# eib-64-large.net
KiCad netlist of a schematic drawn in EAGLE
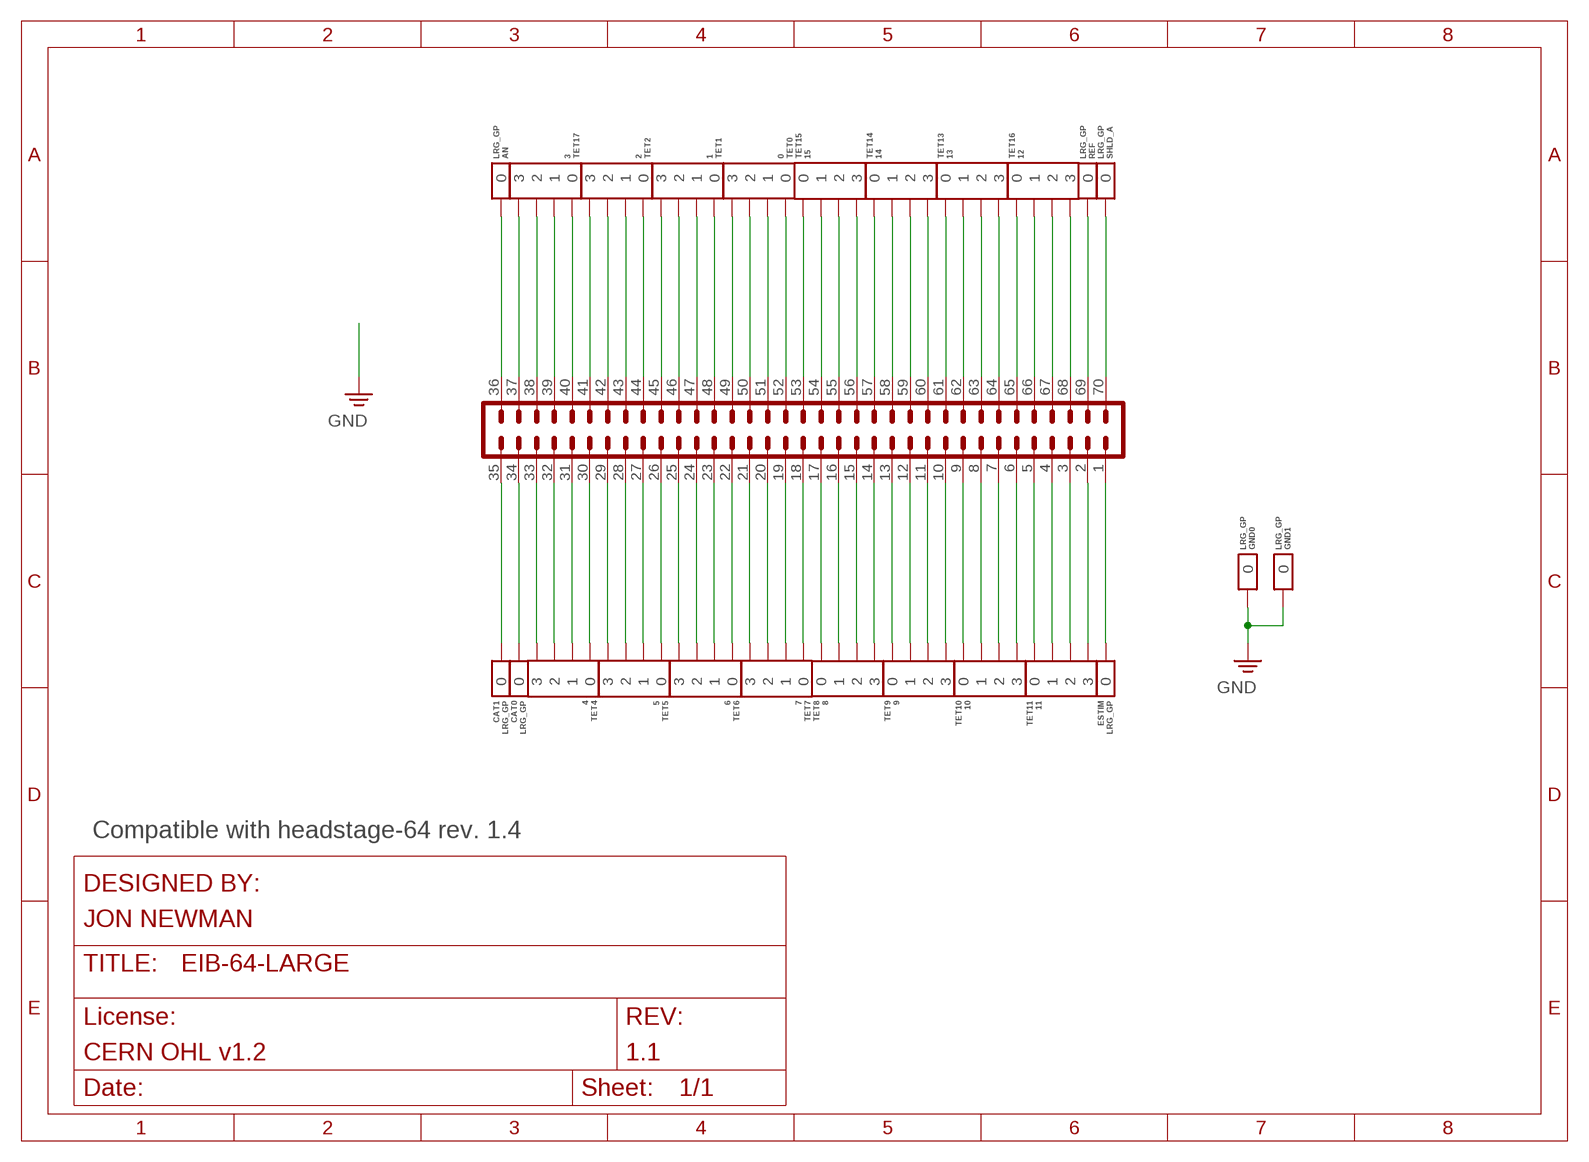
[diagram p0: schematic, sheet 1]

(export (version "E")
  (design (tool "Eeschema 10.0.6"))
  (components
    (comp (ref "AN")
      (value "LRG_GP")
      (footprint "eagle-import:GOLDPIN_0.5ID_0.7OD")
      (libsource (lib "eagle-import") (part "GOLDPIN_0.5ID_0.7OD"))
    )
    (comp (ref "CAT0")
      (value "LRG_GP")
      (footprint "eagle-import:GOLDPIN_0.5ID_0.7OD")
      (libsource (lib "eagle-import") (part "GOLDPIN_0.5ID_0.7OD"))
    )
    (comp (ref "CAT1")
      (value "LRG_GP")
      (footprint "eagle-import:GOLDPIN_0.5ID_0.7OD")
      (libsource (lib "eagle-import") (part "GOLDPIN_0.5ID_0.7OD"))
    )
    (comp (ref "ESTIM")
      (value "LRG_GP")
      (footprint "eagle-import:GOLDPIN_0.5ID_0.7OD")
      (libsource (lib "eagle-import") (part "GOLDPIN_0.5ID_0.7OD"))
    )
    (comp (ref "GND0")
      (value "LRG_GP")
      (footprint "eagle-import:GOLDPIN_0.5ID_0.7OD")
      (libsource (lib "eagle-import") (part "GOLDPIN_0.5ID_0.7OD"))
    )
    (comp (ref "GND1")
      (value "LRG_GP")
      (footprint "eagle-import:GOLDPIN_0.5ID_0.7OD")
      (libsource (lib "eagle-import") (part "GOLDPIN_0.5ID_0.7OD"))
    )
    (comp (ref "J1")
      (value "DF40-REC")
      (footprint "eagle-import:DDF40-70REC-LRG")
      (libsource (lib "eagle-import") (part "PINHD-2X35_DF40REF-LRG"))
    )
    (comp (ref "REF")
      (value "LRG_GP")
      (footprint "eagle-import:GOLDPIN_0.5ID_0.7OD")
      (libsource (lib "eagle-import") (part "GOLDPIN_0.5ID_0.7OD"))
    )
    (comp (ref "SHLD_A")
      (value "LRG_GP")
      (footprint "eagle-import:GOLDPIN_0.5ID_0.7OD")
      (libsource (lib "eagle-import") (part "GOLDPIN_0.5ID_0.7OD"))
    )
    (comp (ref "TET0")
      (value "0")
      (footprint "eagle-import:TETRODE_128_0.5ID_0.7OD")
      (libsource (lib "eagle-import") (part "TETRODE_128_0.5ID_0.7OD"))
    )
    (comp (ref "TET1")
      (value "1")
      (footprint "eagle-import:TETRODE_128_0.5ID_0.7OD")
      (libsource (lib "eagle-import") (part "TETRODE_128_0.5ID_0.7OD"))
    )
    (comp (ref "TET2")
      (value "2")
      (footprint "eagle-import:TETRODE_128_0.5ID_0.7OD")
      (libsource (lib "eagle-import") (part "TETRODE_128_0.5ID_0.7OD"))
    )
    (comp (ref "TET4")
      (value "4")
      (footprint "eagle-import:TETRODE_128_0.5ID_0.7OD")
      (libsource (lib "eagle-import") (part "TETRODE_128_0.5ID_0.7OD"))
    )
    (comp (ref "TET5")
      (value "5")
      (footprint "eagle-import:TETRODE_128_0.5ID_0.7OD")
      (libsource (lib "eagle-import") (part "TETRODE_128_0.5ID_0.7OD"))
    )
    (comp (ref "TET6")
      (value "6")
      (footprint "eagle-import:TETRODE_128_0.5ID_0.7OD")
      (libsource (lib "eagle-import") (part "TETRODE_128_0.5ID_0.7OD"))
    )
    (comp (ref "TET7")
      (value "7")
      (footprint "eagle-import:TETRODE_128_0.5ID_0.7OD")
      (libsource (lib "eagle-import") (part "TETRODE_128_0.5ID_0.7OD"))
    )
    (comp (ref "TET8")
      (value "8")
      (footprint "eagle-import:TETRODE_128_0.5ID_0.7OD")
      (libsource (lib "eagle-import") (part "TETRODE_128_0.5ID_0.7OD"))
    )
    (comp (ref "TET9")
      (value "9")
      (footprint "eagle-import:TETRODE_128_0.5ID_0.7OD")
      (libsource (lib "eagle-import") (part "TETRODE_128_0.5ID_0.7OD"))
    )
    (comp (ref "TET10")
      (value "10")
      (footprint "eagle-import:TETRODE_128_0.5ID_0.7OD")
      (libsource (lib "eagle-import") (part "TETRODE_128_0.5ID_0.7OD"))
    )
    (comp (ref "TET11")
      (value "11")
      (footprint "eagle-import:TETRODE_128_0.5ID_0.7OD")
      (libsource (lib "eagle-import") (part "TETRODE_128_0.5ID_0.7OD"))
    )
    (comp (ref "TET13")
      (value "13")
      (footprint "eagle-import:TETRODE_128_0.5ID_0.7OD")
      (libsource (lib "eagle-import") (part "TETRODE_128_0.5ID_0.7OD"))
    )
    (comp (ref "TET14")
      (value "14")
      (footprint "eagle-import:TETRODE_128_0.5ID_0.7OD")
      (libsource (lib "eagle-import") (part "TETRODE_128_0.5ID_0.7OD"))
    )
    (comp (ref "TET15")
      (value "15")
      (footprint "eagle-import:TETRODE_128_0.5ID_0.7OD")
      (libsource (lib "eagle-import") (part "TETRODE_128_0.5ID_0.7OD"))
    )
    (comp (ref "TET16")
      (value "12")
      (footprint "eagle-import:TETRODE_128_0.5ID_0.7OD")
      (libsource (lib "eagle-import") (part "TETRODE_128_0.5ID_0.7OD"))
    )
    (comp (ref "TET17")
      (value "3")
      (footprint "eagle-import:TETRODE_128_0.5ID_0.7OD")
      (libsource (lib "eagle-import") (part "TETRODE_128_0.5ID_0.7OD"))
    )
  )
  (nets
    (net (code "1") (name "GND") (class "Default")
      (node (ref "GND0") (pin "P$1") (pinfunction "0_P$1") (pintype "bidirectional"))
      (node (ref "GND1") (pin "P$1") (pinfunction "0_P$1") (pintype "bidirectional"))
    )
    (net (code "2") (name "Net-(AN-0)") (class "Default")
      (node (ref "AN") (pin "P$1") (pinfunction "0_P$1") (pintype "bidirectional"))
      (node (ref "J1") (pin "36") (pinfunction "36_36") (pintype "bidirectional"))
    )
    (net (code "3") (name "Net-(CAT0-0)") (class "Default")
      (node (ref "CAT0") (pin "P$1") (pinfunction "0_P$1") (pintype "bidirectional"))
      (node (ref "J1") (pin "34") (pinfunction "34_34") (pintype "bidirectional"))
    )
    (net (code "4") (name "Net-(CAT1-0)") (class "Default")
      (node (ref "CAT1") (pin "P$1") (pinfunction "0_P$1") (pintype "bidirectional"))
      (node (ref "J1") (pin "35") (pinfunction "35_35") (pintype "bidirectional"))
    )
    (net (code "5") (name "Net-(ESTIM-0)") (class "Default")
      (node (ref "ESTIM") (pin "P$1") (pinfunction "0_P$1") (pintype "bidirectional"))
      (node (ref "J1") (pin "1") (pinfunction "1_1") (pintype "bidirectional"))
    )
    (net (code "6") (name "Net-(J1-Pad2)") (class "Default")
      (node (ref "J1") (pin "2") (pinfunction "2_2") (pintype "bidirectional"))
      (node (ref "TET11") (pin "3") (pinfunction "3_3") (pintype "bidirectional"))
    )
    (net (code "7") (name "Net-(J1-Pad3)") (class "Default")
      (node (ref "J1") (pin "3") (pinfunction "3_3") (pintype "bidirectional"))
      (node (ref "TET11") (pin "2") (pinfunction "2_2") (pintype "bidirectional"))
    )
    (net (code "8") (name "Net-(J1-Pad4)") (class "Default")
      (node (ref "J1") (pin "4") (pinfunction "4_4") (pintype "bidirectional"))
      (node (ref "TET11") (pin "1") (pinfunction "1_1") (pintype "bidirectional"))
    )
    (net (code "9") (name "Net-(J1-Pad5)") (class "Default")
      (node (ref "J1") (pin "5") (pinfunction "5_5") (pintype "bidirectional"))
      (node (ref "TET11") (pin "0") (pinfunction "0_0") (pintype "bidirectional"))
    )
    (net (code "10") (name "Net-(J1-Pad6)") (class "Default")
      (node (ref "J1") (pin "6") (pinfunction "6_6") (pintype "bidirectional"))
      (node (ref "TET10") (pin "3") (pinfunction "3_3") (pintype "bidirectional"))
    )
    (net (code "11") (name "Net-(J1-Pad7)") (class "Default")
      (node (ref "J1") (pin "7") (pinfunction "7_7") (pintype "bidirectional"))
      (node (ref "TET10") (pin "2") (pinfunction "2_2") (pintype "bidirectional"))
    )
    (net (code "12") (name "Net-(J1-Pad8)") (class "Default")
      (node (ref "J1") (pin "8") (pinfunction "8_8") (pintype "bidirectional"))
      (node (ref "TET10") (pin "1") (pinfunction "1_1") (pintype "bidirectional"))
    )
    (net (code "13") (name "Net-(J1-Pad9)") (class "Default")
      (node (ref "J1") (pin "9") (pinfunction "9_9") (pintype "bidirectional"))
      (node (ref "TET10") (pin "0") (pinfunction "0_0") (pintype "bidirectional"))
    )
    (net (code "14") (name "Net-(J1-Pad10)") (class "Default")
      (node (ref "J1") (pin "10") (pinfunction "10_10") (pintype "bidirectional"))
      (node (ref "TET9") (pin "3") (pinfunction "3_3") (pintype "bidirectional"))
    )
    (net (code "15") (name "Net-(J1-Pad11)") (class "Default")
      (node (ref "J1") (pin "11") (pinfunction "11_11") (pintype "bidirectional"))
      (node (ref "TET9") (pin "2") (pinfunction "2_2") (pintype "bidirectional"))
    )
    (net (code "16") (name "Net-(J1-Pad12)") (class "Default")
      (node (ref "J1") (pin "12") (pinfunction "12_12") (pintype "bidirectional"))
      (node (ref "TET9") (pin "1") (pinfunction "1_1") (pintype "bidirectional"))
    )
    (net (code "17") (name "Net-(J1-Pad13)") (class "Default")
      (node (ref "J1") (pin "13") (pinfunction "13_13") (pintype "bidirectional"))
      (node (ref "TET9") (pin "0") (pinfunction "0_0") (pintype "bidirectional"))
    )
    (net (code "18") (name "Net-(J1-Pad14)") (class "Default")
      (node (ref "J1") (pin "14") (pinfunction "14_14") (pintype "bidirectional"))
      (node (ref "TET8") (pin "3") (pinfunction "3_3") (pintype "bidirectional"))
    )
    (net (code "19") (name "Net-(J1-Pad15)") (class "Default")
      (node (ref "J1") (pin "15") (pinfunction "15_15") (pintype "bidirectional"))
      (node (ref "TET8") (pin "2") (pinfunction "2_2") (pintype "bidirectional"))
    )
    (net (code "20") (name "Net-(J1-Pad16)") (class "Default")
      (node (ref "J1") (pin "16") (pinfunction "16_16") (pintype "bidirectional"))
      (node (ref "TET8") (pin "1") (pinfunction "1_1") (pintype "bidirectional"))
    )
    (net (code "21") (name "Net-(J1-Pad17)") (class "Default")
      (node (ref "J1") (pin "17") (pinfunction "17_17") (pintype "bidirectional"))
      (node (ref "TET8") (pin "0") (pinfunction "0_0") (pintype "bidirectional"))
    )
    (net (code "22") (name "Net-(J1-Pad18)") (class "Default")
      (node (ref "J1") (pin "18") (pinfunction "18_18") (pintype "bidirectional"))
      (node (ref "TET7") (pin "0") (pinfunction "0_0") (pintype "bidirectional"))
    )
    (net (code "23") (name "Net-(J1-Pad19)") (class "Default")
      (node (ref "J1") (pin "19") (pinfunction "19_19") (pintype "bidirectional"))
      (node (ref "TET7") (pin "1") (pinfunction "1_1") (pintype "bidirectional"))
    )
    (net (code "24") (name "Net-(J1-Pad20)") (class "Default")
      (node (ref "J1") (pin "20") (pinfunction "20_20") (pintype "bidirectional"))
      (node (ref "TET7") (pin "2") (pinfunction "2_2") (pintype "bidirectional"))
    )
    (net (code "25") (name "Net-(J1-Pad21)") (class "Default")
      (node (ref "J1") (pin "21") (pinfunction "21_21") (pintype "bidirectional"))
      (node (ref "TET7") (pin "3") (pinfunction "3_3") (pintype "bidirectional"))
    )
    (net (code "26") (name "Net-(J1-Pad22)") (class "Default")
      (node (ref "J1") (pin "22") (pinfunction "22_22") (pintype "bidirectional"))
      (node (ref "TET6") (pin "0") (pinfunction "0_0") (pintype "bidirectional"))
    )
    (net (code "27") (name "Net-(J1-Pad23)") (class "Default")
      (node (ref "J1") (pin "23") (pinfunction "23_23") (pintype "bidirectional"))
      (node (ref "TET6") (pin "1") (pinfunction "1_1") (pintype "bidirectional"))
    )
    (net (code "28") (name "Net-(J1-Pad24)") (class "Default")
      (node (ref "J1") (pin "24") (pinfunction "24_24") (pintype "bidirectional"))
      (node (ref "TET6") (pin "2") (pinfunction "2_2") (pintype "bidirectional"))
    )
    (net (code "29") (name "Net-(J1-Pad25)") (class "Default")
      (node (ref "J1") (pin "25") (pinfunction "25_25") (pintype "bidirectional"))
      (node (ref "TET6") (pin "3") (pinfunction "3_3") (pintype "bidirectional"))
    )
    (net (code "30") (name "Net-(J1-Pad26)") (class "Default")
      (node (ref "J1") (pin "26") (pinfunction "26_26") (pintype "bidirectional"))
      (node (ref "TET5") (pin "0") (pinfunction "0_0") (pintype "bidirectional"))
    )
    (net (code "31") (name "Net-(J1-Pad27)") (class "Default")
      (node (ref "J1") (pin "27") (pinfunction "27_27") (pintype "bidirectional"))
      (node (ref "TET5") (pin "1") (pinfunction "1_1") (pintype "bidirectional"))
    )
    (net (code "32") (name "Net-(J1-Pad28)") (class "Default")
      (node (ref "J1") (pin "28") (pinfunction "28_28") (pintype "bidirectional"))
      (node (ref "TET5") (pin "2") (pinfunction "2_2") (pintype "bidirectional"))
    )
    (net (code "33") (name "Net-(J1-Pad29)") (class "Default")
      (node (ref "J1") (pin "29") (pinfunction "29_29") (pintype "bidirectional"))
      (node (ref "TET5") (pin "3") (pinfunction "3_3") (pintype "bidirectional"))
    )
    (net (code "34") (name "Net-(J1-Pad30)") (class "Default")
      (node (ref "J1") (pin "30") (pinfunction "30_30") (pintype "bidirectional"))
      (node (ref "TET4") (pin "0") (pinfunction "0_0") (pintype "bidirectional"))
    )
    (net (code "35") (name "Net-(J1-Pad31)") (class "Default")
      (node (ref "J1") (pin "31") (pinfunction "31_31") (pintype "bidirectional"))
      (node (ref "TET4") (pin "1") (pinfunction "1_1") (pintype "bidirectional"))
    )
    (net (code "36") (name "Net-(J1-Pad32)") (class "Default")
      (node (ref "J1") (pin "32") (pinfunction "32_32") (pintype "bidirectional"))
      (node (ref "TET4") (pin "2") (pinfunction "2_2") (pintype "bidirectional"))
    )
    (net (code "37") (name "Net-(J1-Pad33)") (class "Default")
      (node (ref "J1") (pin "33") (pinfunction "33_33") (pintype "bidirectional"))
      (node (ref "TET4") (pin "3") (pinfunction "3_3") (pintype "bidirectional"))
    )
    (net (code "38") (name "Net-(J1-Pad37)") (class "Default")
      (node (ref "J1") (pin "37") (pinfunction "37_37") (pintype "bidirectional"))
      (node (ref "TET17") (pin "3") (pinfunction "3_3") (pintype "bidirectional"))
    )
    (net (code "39") (name "Net-(J1-Pad38)") (class "Default")
      (node (ref "J1") (pin "38") (pinfunction "38_38") (pintype "bidirectional"))
      (node (ref "TET17") (pin "2") (pinfunction "2_2") (pintype "bidirectional"))
    )
    (net (code "40") (name "Net-(J1-Pad39)") (class "Default")
      (node (ref "J1") (pin "39") (pinfunction "39_39") (pintype "bidirectional"))
      (node (ref "TET17") (pin "1") (pinfunction "1_1") (pintype "bidirectional"))
    )
    (net (code "41") (name "Net-(J1-Pad40)") (class "Default")
      (node (ref "J1") (pin "40") (pinfunction "40_40") (pintype "bidirectional"))
      (node (ref "TET17") (pin "0") (pinfunction "0_0") (pintype "bidirectional"))
    )
    (net (code "42") (name "Net-(J1-Pad41)") (class "Default")
      (node (ref "J1") (pin "41") (pinfunction "41_41") (pintype "bidirectional"))
      (node (ref "TET2") (pin "3") (pinfunction "3_3") (pintype "bidirectional"))
    )
    (net (code "43") (name "Net-(J1-Pad42)") (class "Default")
      (node (ref "J1") (pin "42") (pinfunction "42_42") (pintype "bidirectional"))
      (node (ref "TET2") (pin "2") (pinfunction "2_2") (pintype "bidirectional"))
    )
    (net (code "44") (name "Net-(J1-Pad43)") (class "Default")
      (node (ref "J1") (pin "43") (pinfunction "43_43") (pintype "bidirectional"))
      (node (ref "TET2") (pin "1") (pinfunction "1_1") (pintype "bidirectional"))
    )
    (net (code "45") (name "Net-(J1-Pad44)") (class "Default")
      (node (ref "J1") (pin "44") (pinfunction "44_44") (pintype "bidirectional"))
      (node (ref "TET2") (pin "0") (pinfunction "0_0") (pintype "bidirectional"))
    )
    (net (code "46") (name "Net-(J1-Pad45)") (class "Default")
      (node (ref "J1") (pin "45") (pinfunction "45_45") (pintype "bidirectional"))
      (node (ref "TET1") (pin "3") (pinfunction "3_3") (pintype "bidirectional"))
    )
    (net (code "47") (name "Net-(J1-Pad46)") (class "Default")
      (node (ref "J1") (pin "46") (pinfunction "46_46") (pintype "bidirectional"))
      (node (ref "TET1") (pin "2") (pinfunction "2_2") (pintype "bidirectional"))
    )
    (net (code "48") (name "Net-(J1-Pad47)") (class "Default")
      (node (ref "J1") (pin "47") (pinfunction "47_47") (pintype "bidirectional"))
      (node (ref "TET1") (pin "1") (pinfunction "1_1") (pintype "bidirectional"))
    )
    (net (code "49") (name "Net-(J1-Pad48)") (class "Default")
      (node (ref "J1") (pin "48") (pinfunction "48_48") (pintype "bidirectional"))
      (node (ref "TET1") (pin "0") (pinfunction "0_0") (pintype "bidirectional"))
    )
    (net (code "50") (name "Net-(J1-Pad49)") (class "Default")
      (node (ref "J1") (pin "49") (pinfunction "49_49") (pintype "bidirectional"))
      (node (ref "TET0") (pin "3") (pinfunction "3_3") (pintype "bidirectional"))
    )
    (net (code "51") (name "Net-(J1-Pad50)") (class "Default")
      (node (ref "J1") (pin "50") (pinfunction "50_50") (pintype "bidirectional"))
      (node (ref "TET0") (pin "2") (pinfunction "2_2") (pintype "bidirectional"))
    )
    (net (code "52") (name "Net-(J1-Pad51)") (class "Default")
      (node (ref "J1") (pin "51") (pinfunction "51_51") (pintype "bidirectional"))
      (node (ref "TET0") (pin "1") (pinfunction "1_1") (pintype "bidirectional"))
    )
    (net (code "53") (name "Net-(J1-Pad52)") (class "Default")
      (node (ref "J1") (pin "52") (pinfunction "52_52") (pintype "bidirectional"))
      (node (ref "TET0") (pin "0") (pinfunction "0_0") (pintype "bidirectional"))
    )
    (net (code "54") (name "Net-(J1-Pad53)") (class "Default")
      (node (ref "J1") (pin "53") (pinfunction "53_53") (pintype "bidirectional"))
      (node (ref "TET15") (pin "0") (pinfunction "0_0") (pintype "bidirectional"))
    )
    (net (code "55") (name "Net-(J1-Pad54)") (class "Default")
      (node (ref "J1") (pin "54") (pinfunction "54_54") (pintype "bidirectional"))
      (node (ref "TET15") (pin "1") (pinfunction "1_1") (pintype "bidirectional"))
    )
    (net (code "56") (name "Net-(J1-Pad55)") (class "Default")
      (node (ref "J1") (pin "55") (pinfunction "55_55") (pintype "bidirectional"))
      (node (ref "TET15") (pin "2") (pinfunction "2_2") (pintype "bidirectional"))
    )
    (net (code "57") (name "Net-(J1-Pad56)") (class "Default")
      (node (ref "J1") (pin "56") (pinfunction "56_56") (pintype "bidirectional"))
      (node (ref "TET15") (pin "3") (pinfunction "3_3") (pintype "bidirectional"))
    )
    (net (code "58") (name "Net-(J1-Pad57)") (class "Default")
      (node (ref "J1") (pin "57") (pinfunction "57_57") (pintype "bidirectional"))
      (node (ref "TET14") (pin "0") (pinfunction "0_0") (pintype "bidirectional"))
    )
    (net (code "59") (name "Net-(J1-Pad58)") (class "Default")
      (node (ref "J1") (pin "58") (pinfunction "58_58") (pintype "bidirectional"))
      (node (ref "TET14") (pin "1") (pinfunction "1_1") (pintype "bidirectional"))
    )
    (net (code "60") (name "Net-(J1-Pad59)") (class "Default")
      (node (ref "J1") (pin "59") (pinfunction "59_59") (pintype "bidirectional"))
      (node (ref "TET14") (pin "2") (pinfunction "2_2") (pintype "bidirectional"))
    )
    (net (code "61") (name "Net-(J1-Pad60)") (class "Default")
      (node (ref "J1") (pin "60") (pinfunction "60_60") (pintype "bidirectional"))
      (node (ref "TET14") (pin "3") (pinfunction "3_3") (pintype "bidirectional"))
    )
    (net (code "62") (name "Net-(J1-Pad61)") (class "Default")
      (node (ref "J1") (pin "61") (pinfunction "61_61") (pintype "bidirectional"))
      (node (ref "TET13") (pin "0") (pinfunction "0_0") (pintype "bidirectional"))
    )
    (net (code "63") (name "Net-(J1-Pad62)") (class "Default")
      (node (ref "J1") (pin "62") (pinfunction "62_62") (pintype "bidirectional"))
      (node (ref "TET13") (pin "1") (pinfunction "1_1") (pintype "bidirectional"))
    )
    (net (code "64") (name "Net-(J1-Pad63)") (class "Default")
      (node (ref "J1") (pin "63") (pinfunction "63_63") (pintype "bidirectional"))
      (node (ref "TET13") (pin "2") (pinfunction "2_2") (pintype "bidirectional"))
    )
    (net (code "65") (name "Net-(J1-Pad64)") (class "Default")
      (node (ref "J1") (pin "64") (pinfunction "64_64") (pintype "bidirectional"))
      (node (ref "TET13") (pin "3") (pinfunction "3_3") (pintype "bidirectional"))
    )
    (net (code "66") (name "Net-(J1-Pad65)") (class "Default")
      (node (ref "J1") (pin "65") (pinfunction "65_65") (pintype "bidirectional"))
      (node (ref "TET16") (pin "0") (pinfunction "0_0") (pintype "bidirectional"))
    )
    (net (code "67") (name "Net-(J1-Pad66)") (class "Default")
      (node (ref "J1") (pin "66") (pinfunction "66_66") (pintype "bidirectional"))
      (node (ref "TET16") (pin "1") (pinfunction "1_1") (pintype "bidirectional"))
    )
    (net (code "68") (name "Net-(J1-Pad67)") (class "Default")
      (node (ref "J1") (pin "67") (pinfunction "67_67") (pintype "bidirectional"))
      (node (ref "TET16") (pin "2") (pinfunction "2_2") (pintype "bidirectional"))
    )
    (net (code "69") (name "Net-(J1-Pad68)") (class "Default")
      (node (ref "J1") (pin "68") (pinfunction "68_68") (pintype "bidirectional"))
      (node (ref "TET16") (pin "3") (pinfunction "3_3") (pintype "bidirectional"))
    )
    (net (code "70") (name "Net-(REF-0)") (class "Default")
      (node (ref "J1") (pin "69") (pinfunction "69_69") (pintype "bidirectional"))
      (node (ref "REF") (pin "P$1") (pinfunction "0_P$1") (pintype "bidirectional"))
    )
    (net (code "71") (name "Net-(SHLD_A-0)") (class "Default")
      (node (ref "J1") (pin "70") (pinfunction "70_70") (pintype "bidirectional"))
      (node (ref "SHLD_A") (pin "P$1") (pinfunction "0_P$1") (pintype "bidirectional"))
    )
  )
)
